# WZ4827R043-V1_0-20230227.net
KiCad netlist of a schematic drawn in EAGLE
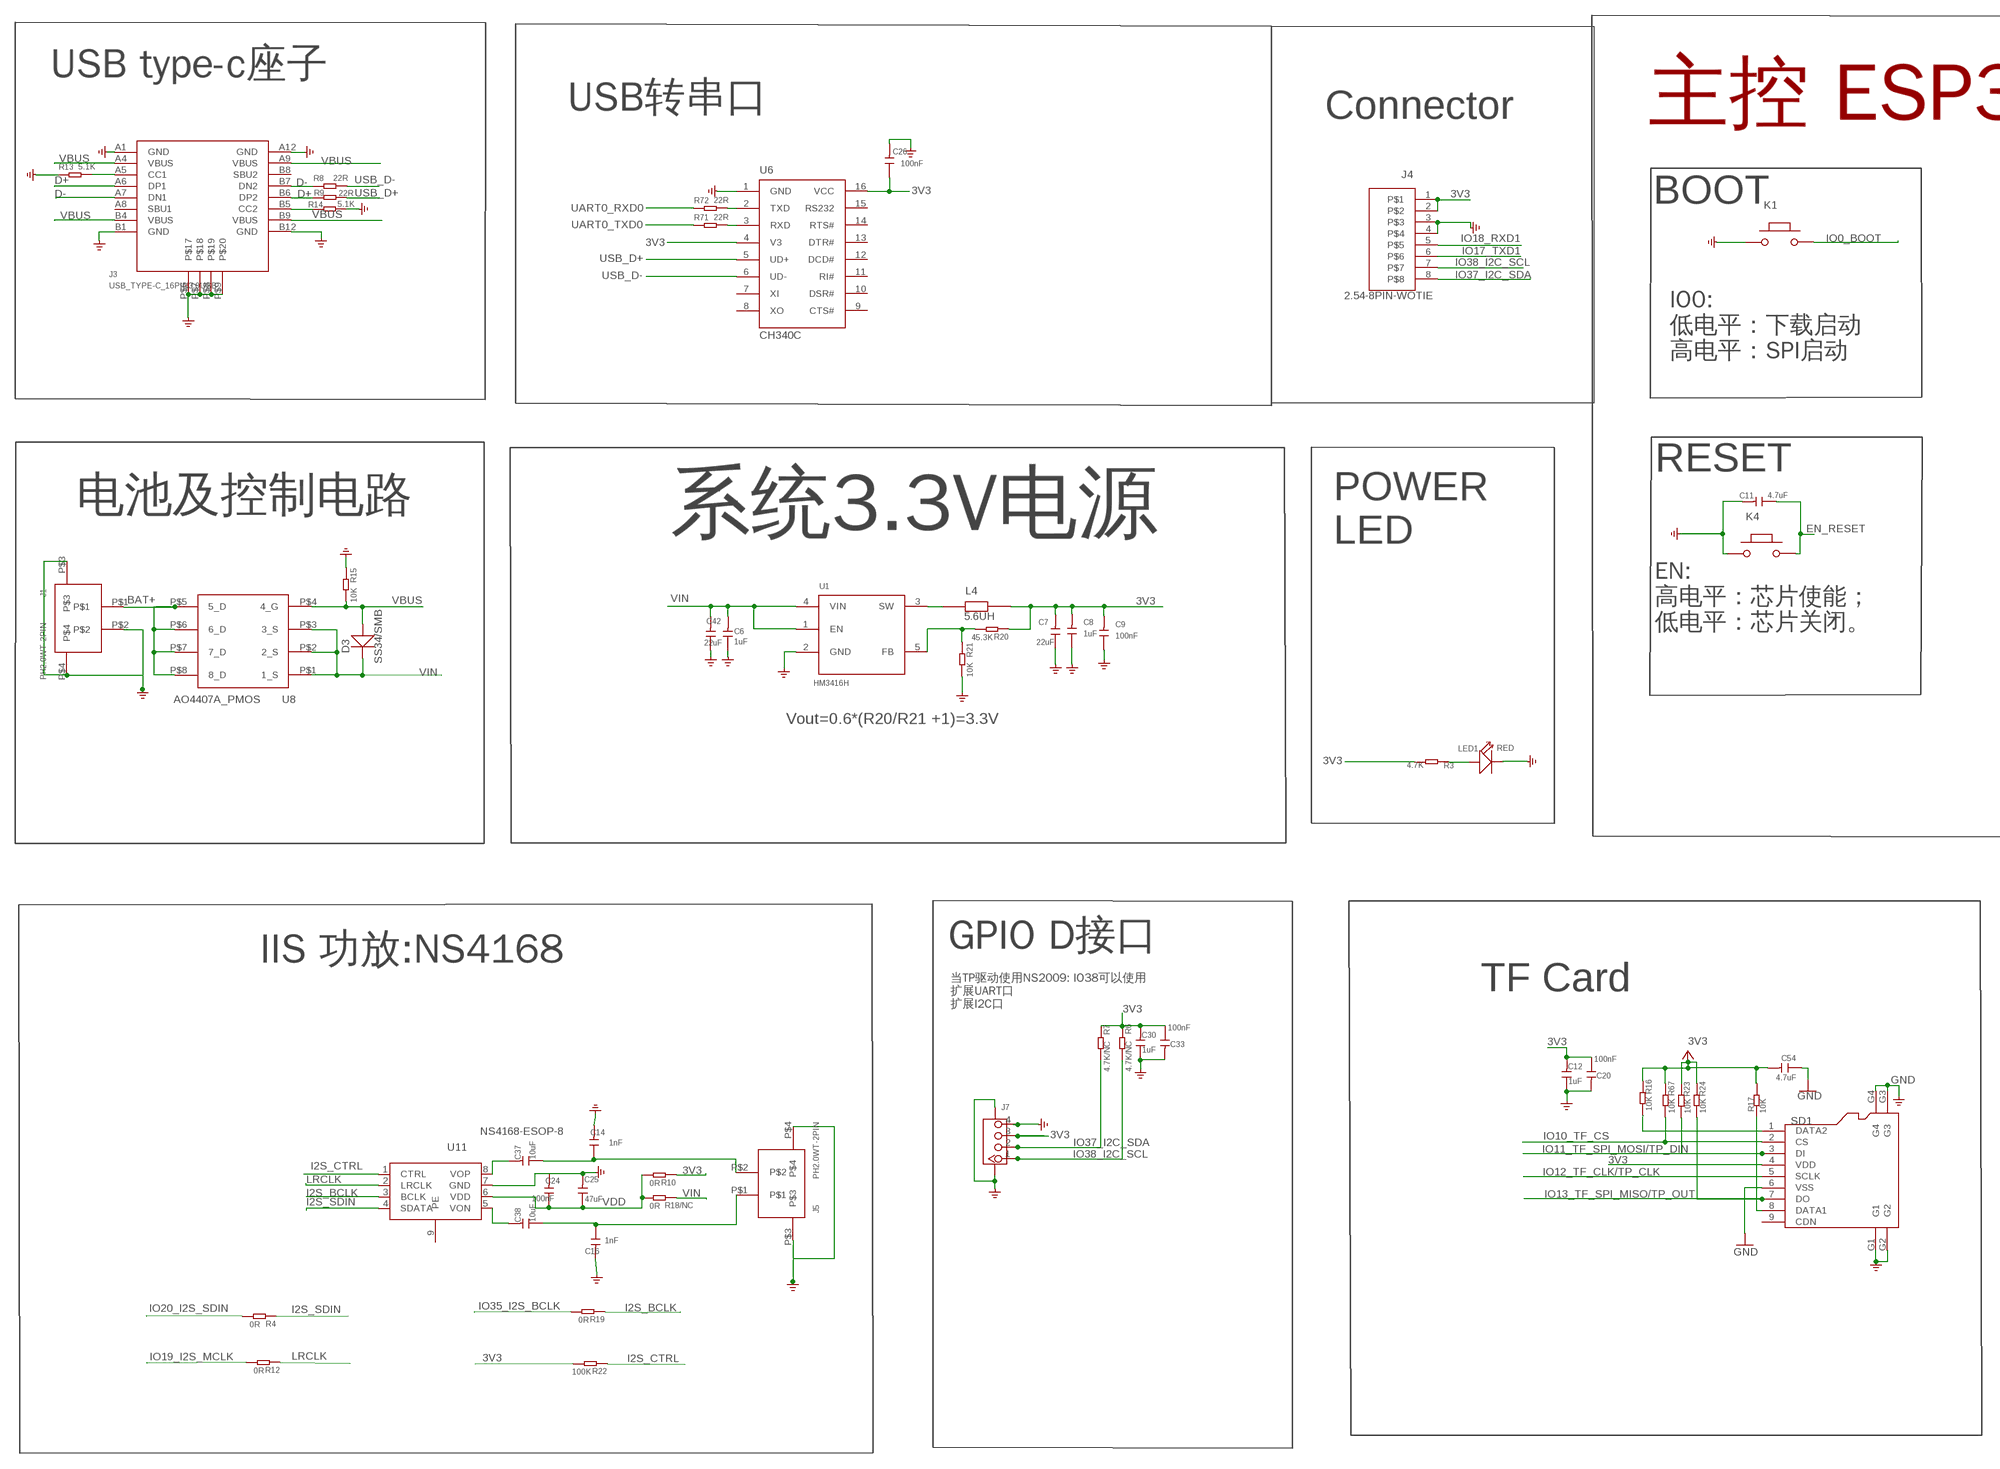
[diagram p0: schematic, sheet 1, part 1 of 2]
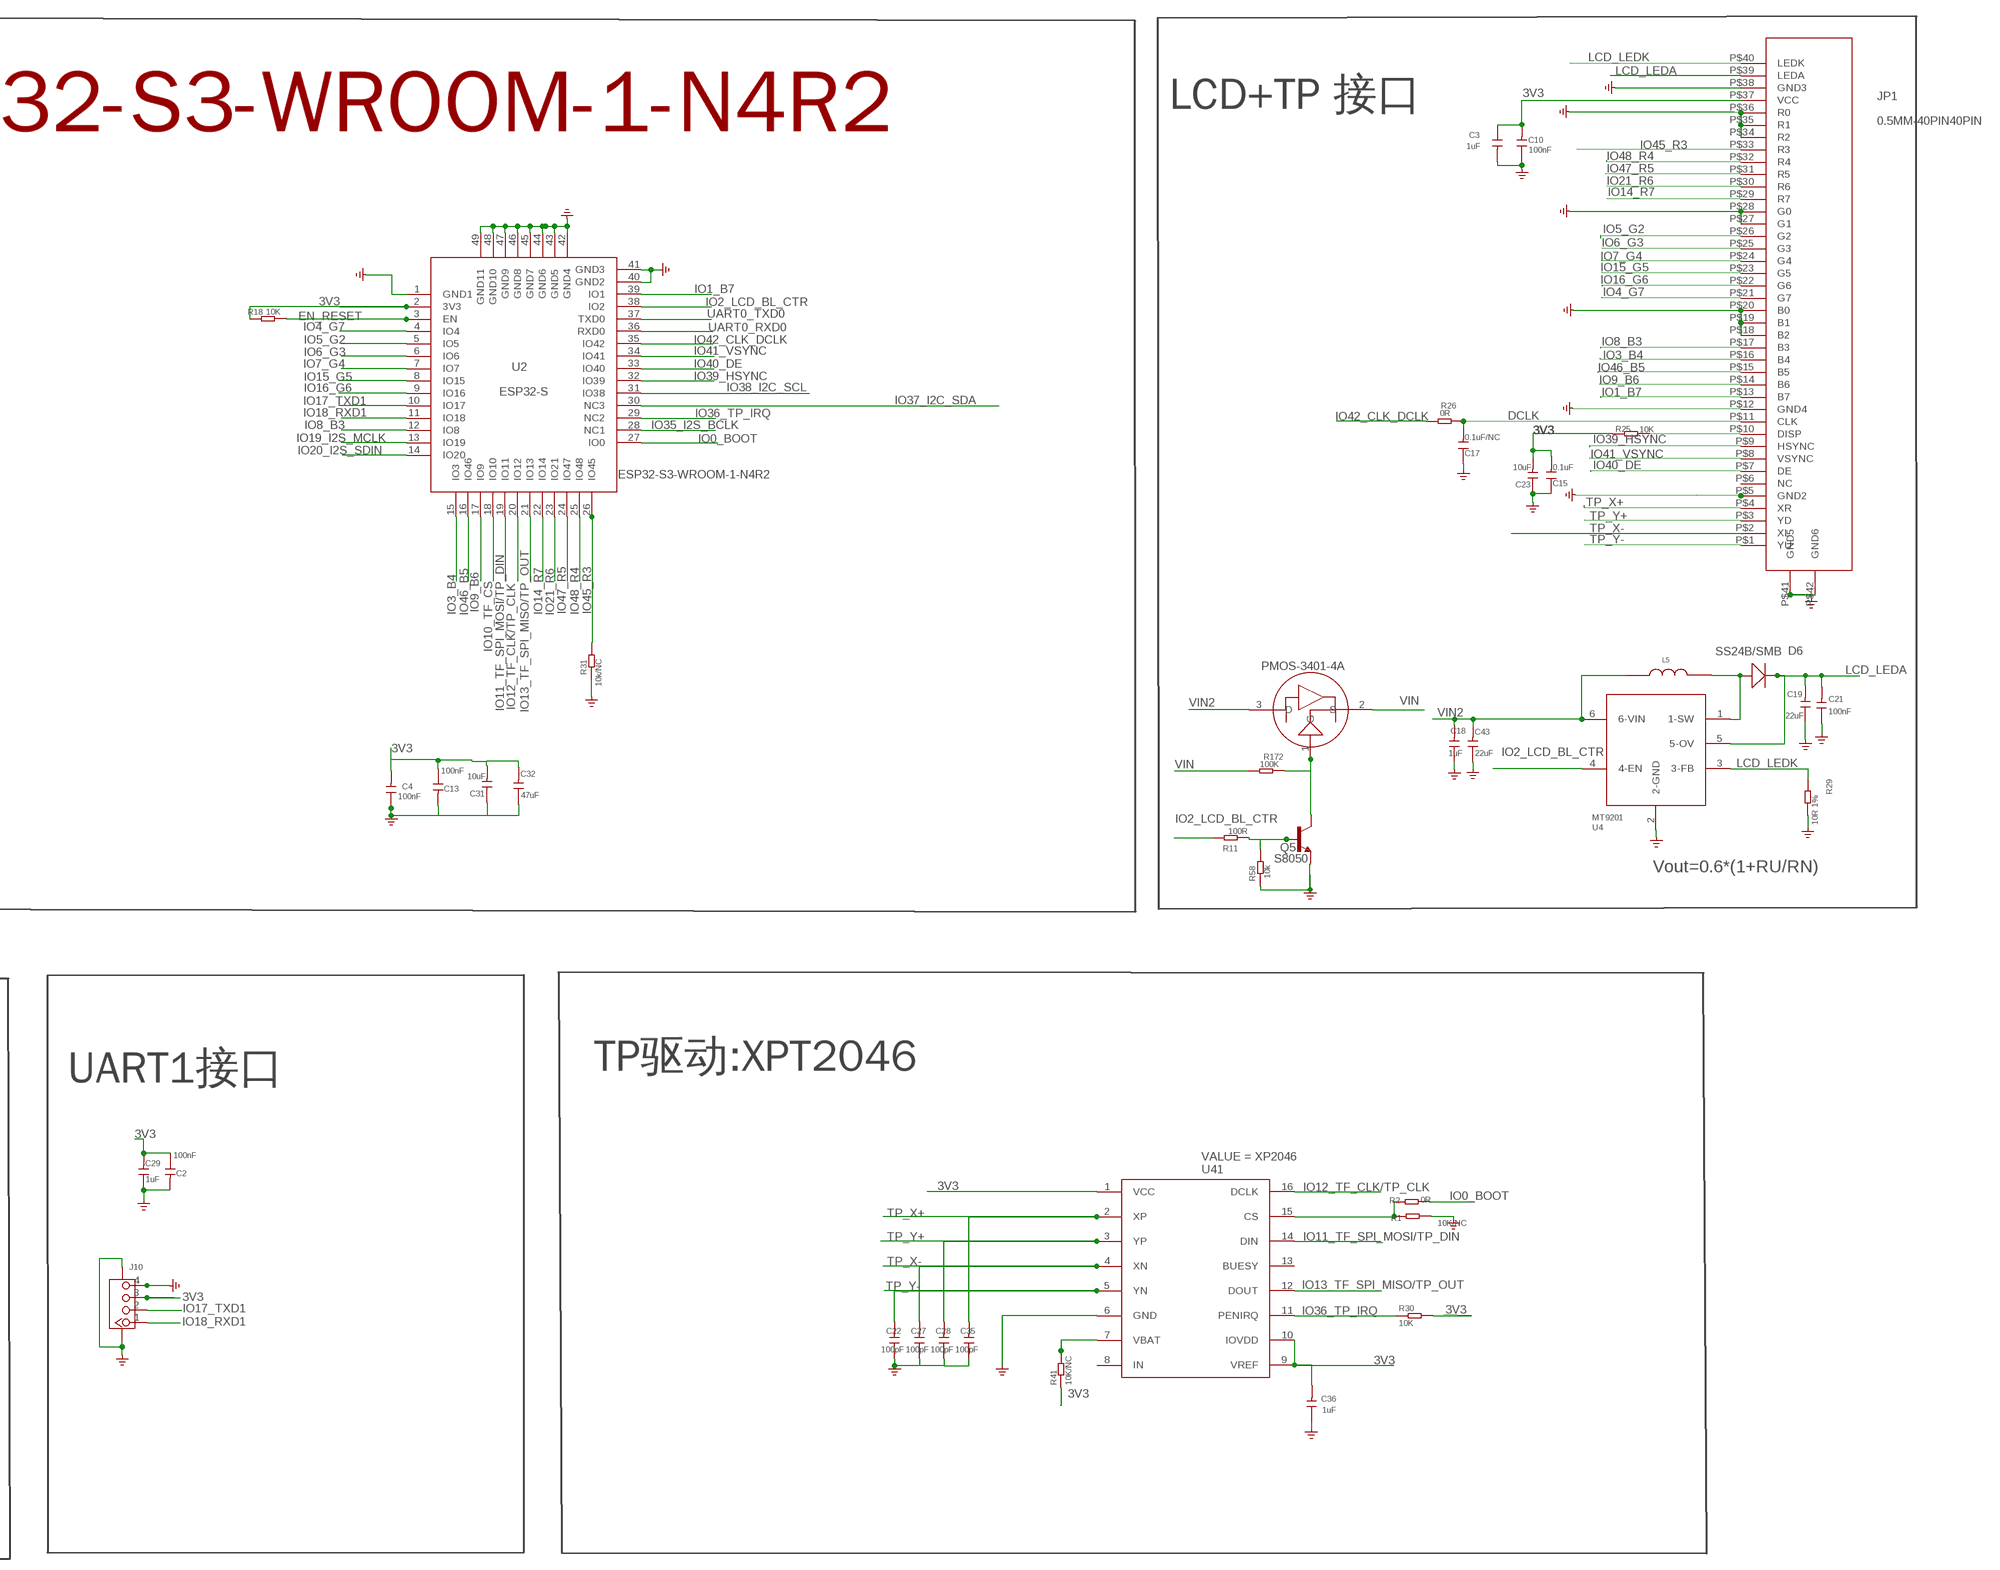
[diagram p1: schematic, sheet 1, part 2 of 2]

(export (version "E")
  (design (tool "Eeschema 10.0.6"))
  (components
    (comp (ref "C2")
      (value "100nF")
      (footprint "eagle-import:C0603")
      (libsource (lib "eagle-import") (part "C-0603"))
    )
    (comp (ref "C3")
      (value "1uF")
      (footprint "eagle-import:C0603")
      (libsource (lib "eagle-import") (part "C-0603"))
    )
    (comp (ref "C4")
      (value "100nF")
      (footprint "eagle-import:C0603")
      (libsource (lib "eagle-import") (part "C-0603"))
    )
    (comp (ref "C6")
      (value "1uF")
      (footprint "eagle-import:0603")
      (libsource (lib "eagle-import") (part "C0603"))
    )
    (comp (ref "C7")
      (value "22uF")
      (footprint "eagle-import:0805")
      (libsource (lib "eagle-import") (part "C0805"))
    )
    (comp (ref "C8")
      (value "1uF")
      (footprint "eagle-import:0603")
      (libsource (lib "eagle-import") (part "C0603"))
    )
    (comp (ref "C9")
      (value "100nF")
      (footprint "eagle-import:0603")
      (libsource (lib "eagle-import") (part "C0603"))
    )
    (comp (ref "C10")
      (value "100nF")
      (footprint "eagle-import:C0603")
      (libsource (lib "eagle-import") (part "C-0603"))
    )
    (comp (ref "C11")
      (value "4.7uF")
      (footprint "eagle-import:0603")
      (libsource (lib "eagle-import") (part "C0603"))
    )
    (comp (ref "C12")
      (value "1uF")
      (footprint "eagle-import:DISCRETE_C0603")
      (libsource (lib "eagle-import") (part "A_xbj_DISCRETE_C-0603"))
    )
    (comp (ref "C13")
      (value "100nF")
      (footprint "eagle-import:C0603")
      (libsource (lib "eagle-import") (part "C-0603"))
    )
    (comp (ref "C14")
      (value "1nF")
      (footprint "eagle-import:C0603")
      (libsource (lib "eagle-import") (part "C-0603"))
    )
    (comp (ref "C15")
      (value "0.1uF")
      (footprint "eagle-import:DISCRETE_C0603")
      (libsource (lib "eagle-import") (part "DISCRETE_C-0603"))
    )
    (comp (ref "C16")
      (value "1nF")
      (footprint "eagle-import:C0603")
      (libsource (lib "eagle-import") (part "C-0603"))
    )
    (comp (ref "C17")
      (value "0.1uF/NC")
      (footprint "eagle-import:DISCRETE_C0603")
      (libsource (lib "eagle-import") (part "DISCRETE_C-0603"))
    )
    (comp (ref "C18")
      (value "1uF")
      (footprint "eagle-import:0603")
      (libsource (lib "eagle-import") (part "C0603"))
    )
    (comp (ref "C19")
      (value "22uF")
      (footprint "eagle-import:0805")
      (libsource (lib "eagle-import") (part "C0805"))
    )
    (comp (ref "C20")
      (value "100nF")
      (footprint "eagle-import:C0603")
      (libsource (lib "eagle-import") (part "C-0603"))
    )
    (comp (ref "C21")
      (value "100nF")
      (footprint "eagle-import:0603")
      (libsource (lib "eagle-import") (part "C0603"))
    )
    (comp (ref "C22")
      (value "100pF")
      (footprint "eagle-import:0603")
      (libsource (lib "eagle-import") (part "C0603"))
    )
    (comp (ref "C23")
      (value "10uF")
      (footprint "eagle-import:DISCRETE_C0603")
      (libsource (lib "eagle-import") (part "DISCRETE_C-0603"))
    )
    (comp (ref "C24")
      (value "100nF")
      (footprint "eagle-import:C0603")
      (libsource (lib "eagle-import") (part "C-0603"))
    )
    (comp (ref "C25")
      (value "47uF")
      (footprint "eagle-import:0805")
      (libsource (lib "eagle-import") (part "C0805"))
    )
    (comp (ref "C26")
      (value "100nF")
      (footprint "eagle-import:0603")
      (libsource (lib "eagle-import") (part "C0603"))
    )
    (comp (ref "C27")
      (value "100pF")
      (footprint "eagle-import:0603")
      (libsource (lib "eagle-import") (part "C0603"))
    )
    (comp (ref "C28")
      (value "100pF")
      (footprint "eagle-import:0603")
      (libsource (lib "eagle-import") (part "C0603"))
    )
    (comp (ref "C29")
      (value "1uF")
      (footprint "eagle-import:DISCRETE_C0603")
      (libsource (lib "eagle-import") (part "A_xbj_DISCRETE_C-0603"))
    )
    (comp (ref "C30")
      (value "1uF")
      (footprint "eagle-import:DISCRETE_C0603")
      (libsource (lib "eagle-import") (part "A_xbj_DISCRETE_C-0603"))
    )
    (comp (ref "C31")
      (value "10uF")
      (footprint "eagle-import:DISCRETE_C0603")
      (libsource (lib "eagle-import") (part "DISCRETE_C-0603"))
    )
    (comp (ref "C32")
      (value "47uF")
      (footprint "eagle-import:0805")
      (libsource (lib "eagle-import") (part "C0805"))
    )
    (comp (ref "C33")
      (value "100nF")
      (footprint "eagle-import:C0603")
      (libsource (lib "eagle-import") (part "C-0603"))
    )
    (comp (ref "C35")
      (value "100pF")
      (footprint "eagle-import:0603")
      (libsource (lib "eagle-import") (part "C0603"))
    )
    (comp (ref "C36")
      (value "1uF")
      (footprint "eagle-import:DISCRETE_C0603")
      (libsource (lib "eagle-import") (part "A_xbj_DISCRETE_C-0603"))
    )
    (comp (ref "C37")
      (value "10uF")
      (footprint "eagle-import:DISCRETE_C0603")
      (libsource (lib "eagle-import") (part "A_xbj_DISCRETE_C-0603"))
    )
    (comp (ref "C38")
      (value "10uF")
      (footprint "eagle-import:DISCRETE_C0603")
      (libsource (lib "eagle-import") (part "A_xbj_DISCRETE_C-0603"))
    )
    (comp (ref "C42")
      (value "22uF")
      (footprint "eagle-import:0805")
      (libsource (lib "eagle-import") (part "C0805"))
    )
    (comp (ref "C43")
      (value "22uF")
      (footprint "eagle-import:0805")
      (libsource (lib "eagle-import") (part "C0805"))
    )
    (comp (ref "C54")
      (value "4.7uF")
      (footprint "eagle-import:DISCRETE_C0603")
      (libsource (lib "eagle-import") (part "DISCRETE_C-0603"))
    )
    (comp (ref "D3")
      (value "SS34/SMB")
      (footprint "eagle-import:214AB")
      (libsource (lib "eagle-import") (part "214ABDO-214AB"))
    )
    (comp (ref "D6")
      (value "SS24B/SMB")
      (footprint "eagle-import:214AB")
      (libsource (lib "eagle-import") (part "214ABDO-214AB"))
    )
    (comp (ref "J1")
      (value "PH2.0WT-2PIN")
      (footprint "eagle-import:PH2.0WT-2PIN")
      (libsource (lib "eagle-import") (part "PH2.0WT-2PIN"))
    )
    (comp (ref "J3")
      (value "USB_TYPE-C_16PIN3.0USB")
      (footprint "eagle-import:KEVIN_3.0TYPEC-SMD")
      (libsource (lib "eagle-import") (part "USB_TYPE-C_16PIN3.0USB"))
    )
    (comp (ref "J4")
      (value "2.54-8PIN-WOTIE")
      (footprint "eagle-import:2.54-8P-WOTIE")
      (libsource (lib "eagle-import") (part "2.54-8PIN-WOTIE"))
    )
    (comp (ref "J5")
      (value "PH2.0WT-2PIN")
      (footprint "eagle-import:PH2.0WT-2PIN")
      (libsource (lib "eagle-import") (part "PH2.0WT-2PIN"))
    )
    (comp (ref "J7")
      (value "CONNECTOR_TWIG-4P-2.0-SMD-FEMALE-REINFORCE90D")
      (footprint "eagle-import:CONNECTOR_4P-SMD-2.0-90D")
      (libsource (lib "eagle-import") (part "CONNECTOR_TWIG-4P-2.0-SMD-FEMALE-REINFORCE90D"))
    )
    (comp (ref "J10")
      (value "CONNECTOR_TWIG-4P-2.0-SMD-FEMALE-REINFORCE90D")
      (footprint "eagle-import:CONNECTOR_4P-SMD-2.0-90D")
      (libsource (lib "eagle-import") (part "CONNECTOR_TWIG-4P-2.0-SMD-FEMALE-REINFORCE90D"))
    )
    (comp (ref "JP1")
      (value "0.5MM-40PIN40PIN")
      (footprint "eagle-import:0.5MM_40P")
      (libsource (lib "eagle-import") (part "0.5MM-40PIN40PIN"))
    )
    (comp (ref "K1")
      (value "BUTTON")
      (footprint "eagle-import:157SW")
      (libsource (lib "eagle-import") (part "PB157"))
    )
    (comp (ref "K4")
      (value "BUTTON")
      (footprint "eagle-import:157SW")
      (libsource (lib "eagle-import") (part "PB157"))
    )
    (comp (ref "L4")
      (value "5.6UH")
      (footprint "eagle-import:CD54")
      (libsource (lib "eagle-import") (part "CROWPI2-MB-V1.4-20211012_CMP201209UD1R0MT"))
    )
    (comp (ref "L5")
      (value "CD32_6.8uH")
      (footprint "eagle-import:CD32")
      (libsource (lib "eagle-import") (part "CD32_950MA"))
    )
    (comp (ref "LED1")
      (value "RED")
      (footprint "eagle-import:DISCRETE_LED-0603")
      (libsource (lib "eagle-import") (part "DISCRETE_LED0603"))
    )
    (comp (ref "Q5")
      (value "S8050")
      (footprint "eagle-import:SPARKFUN_SOT23")
      (libsource (lib "eagle-import") (part "SPARKFUN_TRANSISTOR_NPNSOT23"))
    )
    (comp (ref "Q30")
      (value "PMOS-3401-4A")
      (footprint "eagle-import:SOT-23")
      (libsource (lib "eagle-import") (part "P-MOS-SOT23"))
    )
    (comp (ref "R1")
      (value "10K/NC")
      (footprint "eagle-import:R0603")
      (libsource (lib "eagle-import") (part "R0603"))
    )
    (comp (ref "R2")
      (value "0R")
      (footprint "eagle-import:DISCRETE_R0603")
      (libsource (lib "eagle-import") (part "Crowtail-_LED-V2.0-20190615-01_DISCRETE_R-0603"))
    )
    (comp (ref "R3")
      (value "4.7K")
      (footprint "eagle-import:DISCRETE_R0603")
      (libsource (lib "eagle-import") (part "Crowtail-_LED-V2.0-20190615-01_DISCRETE_R-0603"))
    )
    (comp (ref "R4")
      (value "0R")
      (footprint "eagle-import:DISCRETE_R0603")
      (libsource (lib "eagle-import") (part "Crowtail-_LED-V2.0-20190615-01_DISCRETE_R-0603"))
    )
    (comp (ref "R6")
      (value "4.7K/NC")
      (footprint "eagle-import:DISCRETE_R0603")
      (libsource (lib "eagle-import") (part "Crowtail-_LED-V2.0-20190615-01_DISCRETE_R-0603"))
    )
    (comp (ref "R7")
      (value "4.7K/NC")
      (footprint "eagle-import:DISCRETE_R0603")
      (libsource (lib "eagle-import") (part "Crowtail-_LED-V2.0-20190615-01_DISCRETE_R-0603"))
    )
    (comp (ref "R8")
      (value "22R")
      (footprint "eagle-import:DISCRETE_R0603")
      (libsource (lib "eagle-import") (part "Crowtail-_LED-V2.0-20190615-01_DISCRETE_R-0603"))
    )
    (comp (ref "R9")
      (value "22R")
      (footprint "eagle-import:DISCRETE_R0603")
      (libsource (lib "eagle-import") (part "Crowtail-_LED-V2.0-20190615-01_DISCRETE_R-0603"))
    )
    (comp (ref "R10")
      (value "0R")
      (footprint "eagle-import:DISCRETE_R0603")
      (libsource (lib "eagle-import") (part "Crowtail-_LED-V2.0-20190615-01_DISCRETE_R-0603"))
    )
    (comp (ref "R11")
      (value "100R")
      (footprint "eagle-import:R0603")
      (libsource (lib "eagle-import") (part "R0603"))
    )
    (comp (ref "R12")
      (value "0R")
      (footprint "eagle-import:DISCRETE_R0603")
      (libsource (lib "eagle-import") (part "Crowtail-_LED-V2.0-20190615-01_DISCRETE_R-0603"))
    )
    (comp (ref "R13")
      (value "5.1K")
      (footprint "eagle-import:DISCRETE_R0603")
      (libsource (lib "eagle-import") (part "Crowtail-_LED-V2.0-20190615-01_DISCRETE_R-0603"))
    )
    (comp (ref "R14")
      (value "5.1K")
      (footprint "eagle-import:DISCRETE_R0603")
      (libsource (lib "eagle-import") (part "Crowtail-_LED-V2.0-20190615-01_DISCRETE_R-0603"))
    )
    (comp (ref "R15")
      (value "10K")
      (footprint "eagle-import:DISCRETE_R0603")
      (libsource (lib "eagle-import") (part "Crowtail-_LED-V2.0-20190615-01_DISCRETE_R-0603"))
    )
    (comp (ref "R16")
      (value "10K")
      (footprint "eagle-import:DISCRETE_R0603")
      (libsource (lib "eagle-import") (part "Crowtail-_LED-V2.0-20190615-01_DISCRETE_R-0603"))
    )
    (comp (ref "R17")
      (value "10K")
      (footprint "eagle-import:DISCRETE_R0603")
      (libsource (lib "eagle-import") (part "Crowtail-_LED-V2.0-20190615-01_DISCRETE_R-0603"))
    )
    (comp (ref "R18")
      (value "10K")
      (footprint "eagle-import:DISCRETE_R0603")
      (libsource (lib "eagle-import") (part "Crowtail-_LED-V2.0-20190615-01_DISCRETE_R-0603"))
    )
    (comp (ref "R18/NC")
      (value "0R")
      (footprint "eagle-import:DISCRETE_R0603")
      (libsource (lib "eagle-import") (part "Crowtail-_LED-V2.0-20190615-01_DISCRETE_R-0603"))
    )
    (comp (ref "R19")
      (value "0R")
      (footprint "eagle-import:DISCRETE_R0603")
      (libsource (lib "eagle-import") (part "Crowtail-_LED-V2.0-20190615-01_DISCRETE_R-0603"))
    )
    (comp (ref "R20")
      (value "45.3K")
      (footprint "eagle-import:DISCRETE_R0603")
      (libsource (lib "eagle-import") (part "Crowtail-_LED-V2.0-20190615-01_DISCRETE_R-0603"))
    )
    (comp (ref "R21")
      (value "10K")
      (footprint "eagle-import:DISCRETE_R0603")
      (libsource (lib "eagle-import") (part "Crowtail-_LED-V2.0-20190615-01_DISCRETE_R-0603"))
    )
    (comp (ref "R22")
      (value "100K")
      (footprint "eagle-import:DISCRETE_R0603")
      (libsource (lib "eagle-import") (part "Crowtail-_LED-V2.0-20190615-01_DISCRETE_R-0603"))
    )
    (comp (ref "R23")
      (value "10K")
      (footprint "eagle-import:DISCRETE_R0603")
      (libsource (lib "eagle-import") (part "Crowtail-_LED-V2.0-20190615-01_DISCRETE_R-0603"))
    )
    (comp (ref "R24")
      (value "10K")
      (footprint "eagle-import:DISCRETE_R0603")
      (libsource (lib "eagle-import") (part "Crowtail-_LED-V2.0-20190615-01_DISCRETE_R-0603"))
    )
    (comp (ref "R25")
      (value "10K")
      (footprint "eagle-import:DISCRETE_R0603")
      (libsource (lib "eagle-import") (part "Crowtail-_LED-V2.0-20190615-01_DISCRETE_R-0603"))
    )
    (comp (ref "R26")
      (value "0R")
      (footprint "eagle-import:R0603")
      (libsource (lib "eagle-import") (part "R-0603"))
    )
    (comp (ref "R29")
      (value "10R 1%")
      (footprint "eagle-import:DISCRETE_R0603")
      (libsource (lib "eagle-import") (part "Crowtail-_LED-V2.0-20190615-01_DISCRETE_R-0603"))
    )
    (comp (ref "R30")
      (value "10K")
      (footprint "eagle-import:DISCRETE_R0603")
      (libsource (lib "eagle-import") (part "DISCRETE_R-0603"))
    )
    (comp (ref "R31")
      (value "10k/NC")
      (footprint "eagle-import:R0603")
      (libsource (lib "eagle-import") (part "R0603"))
    )
    (comp (ref "R41")
      (value "10K/NC")
      (footprint "eagle-import:DISCRETE_R0603")
      (libsource (lib "eagle-import") (part "DISCRETE_R-0603"))
    )
    (comp (ref "R58")
      (value "10k")
      (footprint "eagle-import:R0603")
      (libsource (lib "eagle-import") (part "R0603"))
    )
    (comp (ref "R67")
      (value "10K")
      (footprint "eagle-import:DISCRETE_R0603")
      (libsource (lib "eagle-import") (part "Crowtail-_LED-V2.0-20190615-01_DISCRETE_R-0603"))
    )
    (comp (ref "R71")
      (value "22R")
      (footprint "eagle-import:DISCRETE_R0603")
      (libsource (lib "eagle-import") (part "Crowtail-_LED-V2.0-20190615-01_DISCRETE_R-0603"))
    )
    (comp (ref "R72")
      (value "22R")
      (footprint "eagle-import:DISCRETE_R0603")
      (libsource (lib "eagle-import") (part "Crowtail-_LED-V2.0-20190615-01_DISCRETE_R-0603"))
    )
    (comp (ref "R172")
      (value "100K")
      (footprint "eagle-import:R0603")
      (libsource (lib "eagle-import") (part "R-0603"))
    )
    (comp (ref "SD1")
      (value "HOLDER-MICROSD-9P")
      (footprint "eagle-import:9P-SMD-W_-RING")
      (libsource (lib "eagle-import") (part "HOLDER-MICROSD-9P"))
    )
    (comp (ref "U1")
      (value "HM3416H")
      (footprint "eagle-import:A_XBJ_SOT23-5")
      (libsource (lib "eagle-import") (part "A_XBJ_HM3420B"))
    )
    (comp (ref "U2")
      (value "ESP32-S")
      (footprint "eagle-import:ESP32-S3")
      (fields (field (name "U2") "ESP32-S3-WROOM-1-N4R2"))
      (libsource (lib "eagle-import") (part "ESP32-S"))
    )
    (comp (ref "U4")
      (value "MT9201")
      (footprint "eagle-import:SOT23-6")
      (libsource (lib "eagle-import") (part "MT9201"))
    )
    (comp (ref "U6")
      (value "CH340C")
      (footprint "eagle-import:SOP-16")
      (libsource (lib "eagle-import") (part "CH340G"))
    )
    (comp (ref "U8")
      (value "AO4407A_PMOS")
      (footprint "eagle-import:SOP8")
      (libsource (lib "eagle-import") (part "T_PMOS_AO4407A_SOP8"))
    )
    (comp (ref "U11")
      (value "NS4168-ESOP-8")
      (footprint "eagle-import:NS4168-ESOP-8")
      (libsource (lib "eagle-import") (part "NS4168-ESOP-8"))
    )
    (comp (ref "U41")
      (value "XP2046")
      (footprint "eagle-import:XP2046-SSOP16")
      (libsource (lib "eagle-import") (part "XP2046"))
    )
  )
  (nets
    (net (code "1") (name "+3V3") (class "Default")
      (node (ref "C10") (pin "2") (pinfunction "2_2") (pintype "passive"))
      (node (ref "C12") (pin "2") (pinfunction "2_2") (pintype "passive"))
      (node (ref "C13") (pin "1") (pinfunction "1_1") (pintype "passive"))
      (node (ref "C15") (pin "2") (pinfunction "2_2") (pintype "passive"))
      (node (ref "C2") (pin "1") (pinfunction "1_1") (pintype "passive"))
      (node (ref "C20") (pin "1") (pinfunction "1_1") (pintype "passive"))
      (node (ref "C23") (pin "2") (pinfunction "2_2") (pintype "passive"))
      (node (ref "C26") (pin "1") (pinfunction "1_1") (pintype "passive"))
      (node (ref "C29") (pin "2") (pinfunction "2_2") (pintype "passive"))
      (node (ref "C3") (pin "1") (pinfunction "1_1") (pintype "passive"))
      (node (ref "C30") (pin "2") (pinfunction "2_2") (pintype "passive"))
      (node (ref "C31") (pin "2") (pinfunction "2_2") (pintype "passive"))
      (node (ref "C32") (pin "2") (pinfunction "2_2") (pintype "passive"))
      (node (ref "C33") (pin "1") (pinfunction "1_1") (pintype "passive"))
      (node (ref "C36") (pin "2") (pinfunction "2_2") (pintype "passive"))
      (node (ref "C4") (pin "2") (pinfunction "2_2") (pintype "passive"))
      (node (ref "C54") (pin "2") (pinfunction "2_2") (pintype "passive"))
      (node (ref "C7") (pin "2") (pinfunction "2_2") (pintype "passive"))
      (node (ref "C8") (pin "2") (pinfunction "2_2") (pintype "passive"))
      (node (ref "C9") (pin "2") (pinfunction "2_2") (pintype "passive"))
      (node (ref "J10") (pin "3") (pinfunction "3_3") (pintype "bidirectional"))
      (node (ref "J4") (pin "1") (pinfunction "P$1_1") (pintype "bidirectional"))
      (node (ref "J4") (pin "2") (pinfunction "P$2_2") (pintype "bidirectional"))
      (node (ref "J7") (pin "3") (pinfunction "3_3") (pintype "bidirectional"))
      (node (ref "JP1") (pin "P$37") (pinfunction "VCC_P$37") (pintype "bidirectional"))
      (node (ref "L4") (pin "2") (pinfunction "2_2") (pintype "bidirectional"))
      (node (ref "R10") (pin "1") (pinfunction "1_1") (pintype "passive"))
      (node (ref "R16") (pin "1") (pinfunction "1_1") (pintype "passive"))
      (node (ref "R17") (pin "1") (pinfunction "1_1") (pintype "passive"))
      (node (ref "R18") (pin "1") (pinfunction "1_1") (pintype "passive"))
      (node (ref "R20") (pin "1") (pinfunction "1_1") (pintype "passive"))
      (node (ref "R22") (pin "2") (pinfunction "2_2") (pintype "passive"))
      (node (ref "R23") (pin "1") (pinfunction "1_1") (pintype "passive"))
      (node (ref "R24") (pin "1") (pinfunction "1_1") (pintype "passive"))
      (node (ref "R25") (pin "1") (pinfunction "1_1") (pintype "passive"))
      (node (ref "R3") (pin "2") (pinfunction "2_2") (pintype "passive"))
      (node (ref "R30") (pin "2") (pinfunction "2_2") (pintype "passive"))
      (node (ref "R41") (pin "1") (pinfunction "1_1") (pintype "passive"))
      (node (ref "R6") (pin "1") (pinfunction "1_1") (pintype "passive"))
      (node (ref "R67") (pin "1") (pinfunction "1_1") (pintype "passive"))
      (node (ref "R7") (pin "1") (pinfunction "1_1") (pintype "passive"))
      (node (ref "SD1") (pin "4") (pinfunction "VDD_4") (pintype "bidirectional"))
      (node (ref "U2") (pin "2") (pinfunction "3V3_2") (pintype "bidirectional"))
      (node (ref "U41") (pin "1") (pinfunction "VCC_1") (pintype "bidirectional"))
      (node (ref "U41") (pin "10") (pinfunction "IOVDD_10") (pintype "bidirectional"))
      (node (ref "U41") (pin "9") (pinfunction "VREF_9") (pintype "bidirectional"))
      (node (ref "U6") (pin "16") (pinfunction "VCC_16") (pintype "bidirectional"))
      (node (ref "U6") (pin "4") (pinfunction "V3_4") (pintype "bidirectional"))
    )
    (net (code "2") (name "/BAT+") (class "Default")
      (node (ref "J1") (pin "P$1") (pinfunction "P$1_P$1") (pintype "bidirectional"))
      (node (ref "U8") (pin "P$5") (pinfunction "5_D_P$5") (pintype "bidirectional"))
      (node (ref "U8") (pin "P$6") (pinfunction "6_D_P$6") (pintype "bidirectional"))
      (node (ref "U8") (pin "P$7") (pinfunction "7_D_P$7") (pintype "bidirectional"))
      (node (ref "U8") (pin "P$8") (pinfunction "8_D_P$8") (pintype "bidirectional"))
    )
    (net (code "3") (name "/D+") (class "Default")
      (node (ref "J3") (pin "A6") (pinfunction "DP1_A6") (pintype "bidirectional"))
      (node (ref "J3") (pin "B6") (pinfunction "DP2_B6") (pintype "bidirectional"))
      (node (ref "R9") (pin "1") (pinfunction "1_1") (pintype "passive"))
    )
    (net (code "4") (name "/D-") (class "Default")
      (node (ref "J3") (pin "A7") (pinfunction "DN1_A7") (pintype "bidirectional"))
      (node (ref "J3") (pin "B7") (pinfunction "DN2_B7") (pintype "bidirectional"))
      (node (ref "R8") (pin "1") (pinfunction "1_1") (pintype "passive"))
    )
    (net (code "5") (name "/DCLK") (class "Default")
      (node (ref "C17") (pin "2") (pinfunction "2_2") (pintype "passive"))
      (node (ref "JP1") (pin "P$11") (pinfunction "CLK_P$11") (pintype "bidirectional"))
      (node (ref "R26") (pin "2") (pinfunction "2_2") (pintype "passive"))
    )
    (net (code "6") (name "/EN_RESET") (class "Default")
      (node (ref "C11") (pin "1") (pinfunction "1_1") (pintype "passive"))
      (node (ref "K4") (pin "2") (pinfunction "2_2") (pintype "passive"))
      (node (ref "R18") (pin "2") (pinfunction "2_2") (pintype "passive"))
      (node (ref "U2") (pin "3") (pinfunction "EN_3") (pintype "bidirectional"))
    )
    (net (code "7") (name "/I2S_BCLK") (class "Default")
      (node (ref "R19") (pin "1") (pinfunction "1_1") (pintype "passive"))
      (node (ref "U11") (pin "3") (pinfunction "BCLK_3") (pintype "bidirectional"))
    )
    (net (code "8") (name "/I2S_CTRL") (class "Default")
      (node (ref "R22") (pin "1") (pinfunction "1_1") (pintype "passive"))
      (node (ref "U11") (pin "1") (pinfunction "CTRL_1") (pintype "bidirectional"))
    )
    (net (code "9") (name "/I2S_SDIN") (class "Default")
      (node (ref "R4") (pin "1") (pinfunction "1_1") (pintype "passive"))
      (node (ref "U11") (pin "4") (pinfunction "SDATA_4") (pintype "bidirectional"))
    )
    (net (code "10") (name "/IO0_BOOT") (class "Default")
      (node (ref "K1") (pin "2") (pinfunction "2_2") (pintype "passive"))
      (node (ref "R2") (pin "1") (pinfunction "1_1") (pintype "passive"))
      (node (ref "U2") (pin "27") (pinfunction "IO0_27") (pintype "bidirectional"))
    )
    (net (code "11") (name "/IO1_B7") (class "Default")
      (node (ref "JP1") (pin "P$13") (pinfunction "B7_P$13") (pintype "bidirectional"))
      (node (ref "U2") (pin "39") (pinfunction "IO1_39") (pintype "bidirectional"))
    )
    (net (code "12") (name "/IO2_LCD_BL_CTR") (class "Default")
      (node (ref "R11") (pin "2") (pinfunction "2_2") (pintype "passive"))
      (node (ref "U2") (pin "38") (pinfunction "IO2_38") (pintype "bidirectional"))
      (node (ref "U4") (pin "4") (pinfunction "4-EN_4") (pintype "bidirectional"))
    )
    (net (code "13") (name "/IO3_B4") (class "Default")
      (node (ref "JP1") (pin "P$16") (pinfunction "B4_P$16") (pintype "bidirectional"))
      (node (ref "U2") (pin "15") (pinfunction "IO3_15") (pintype "bidirectional"))
    )
    (net (code "14") (name "/IO4_G7") (class "Default")
      (node (ref "JP1") (pin "P$21") (pinfunction "G7_P$21") (pintype "bidirectional"))
      (node (ref "U2") (pin "4") (pinfunction "IO4_4") (pintype "bidirectional"))
    )
    (net (code "15") (name "/IO5_G2") (class "Default")
      (node (ref "JP1") (pin "P$26") (pinfunction "G2_P$26") (pintype "bidirectional"))
      (node (ref "U2") (pin "5") (pinfunction "IO5_5") (pintype "bidirectional"))
    )
    (net (code "16") (name "/IO6_G3") (class "Default")
      (node (ref "JP1") (pin "P$25") (pinfunction "G3_P$25") (pintype "bidirectional"))
      (node (ref "U2") (pin "6") (pinfunction "IO6_6") (pintype "bidirectional"))
    )
    (net (code "17") (name "/IO7_G4") (class "Default")
      (node (ref "JP1") (pin "P$24") (pinfunction "G4_P$24") (pintype "bidirectional"))
      (node (ref "U2") (pin "7") (pinfunction "IO7_7") (pintype "bidirectional"))
    )
    (net (code "18") (name "/IO8_B3") (class "Default")
      (node (ref "JP1") (pin "P$17") (pinfunction "B3_P$17") (pintype "bidirectional"))
      (node (ref "U2") (pin "12") (pinfunction "IO8_12") (pintype "bidirectional"))
    )
    (net (code "19") (name "/IO9_B6") (class "Default")
      (node (ref "JP1") (pin "P$14") (pinfunction "B6_P$14") (pintype "bidirectional"))
      (node (ref "U2") (pin "17") (pinfunction "IO9_17") (pintype "bidirectional"))
    )
    (net (code "20") (name "/IO10_TF_CS") (class "Default")
      (node (ref "R67") (pin "2") (pinfunction "2_2") (pintype "passive"))
      (node (ref "SD1") (pin "2") (pinfunction "CS_2") (pintype "bidirectional"))
      (node (ref "U2") (pin "18") (pinfunction "IO10_18") (pintype "bidirectional"))
    )
    (net (code "21") (name "/IO11_TF_SPI_MOSI{slash}TP_DIN") (class "Default")
      (node (ref "R23") (pin "2") (pinfunction "2_2") (pintype "passive"))
      (node (ref "SD1") (pin "3") (pinfunction "DI_3") (pintype "bidirectional"))
      (node (ref "U2") (pin "19") (pinfunction "IO11_19") (pintype "bidirectional"))
      (node (ref "U41") (pin "14") (pinfunction "DIN_14") (pintype "bidirectional"))
    )
    (net (code "22") (name "/IO12_TF_CLK{slash}TP_CLK") (class "Default")
      (node (ref "SD1") (pin "5") (pinfunction "SCLK_5") (pintype "bidirectional"))
      (node (ref "U2") (pin "20") (pinfunction "IO12_20") (pintype "bidirectional"))
      (node (ref "U41") (pin "16") (pinfunction "DCLK_16") (pintype "bidirectional"))
    )
    (net (code "23") (name "/IO13_TF_SPI_MISO{slash}TP_OUT") (class "Default")
      (node (ref "R24") (pin "2") (pinfunction "2_2") (pintype "passive"))
      (node (ref "SD1") (pin "7") (pinfunction "DO_7") (pintype "bidirectional"))
      (node (ref "U2") (pin "21") (pinfunction "IO13_21") (pintype "bidirectional"))
      (node (ref "U41") (pin "12") (pinfunction "DOUT_12") (pintype "bidirectional"))
    )
    (net (code "24") (name "/IO14_R7") (class "Default")
      (node (ref "JP1") (pin "P$29") (pinfunction "R7_P$29") (pintype "bidirectional"))
      (node (ref "U2") (pin "22") (pinfunction "IO14_22") (pintype "bidirectional"))
    )
    (net (code "25") (name "/IO15_G5") (class "Default")
      (node (ref "JP1") (pin "P$23") (pinfunction "G5_P$23") (pintype "bidirectional"))
      (node (ref "U2") (pin "8") (pinfunction "IO15_8") (pintype "bidirectional"))
    )
    (net (code "26") (name "/IO16_G6") (class "Default")
      (node (ref "JP1") (pin "P$22") (pinfunction "G6_P$22") (pintype "bidirectional"))
      (node (ref "U2") (pin "9") (pinfunction "IO16_9") (pintype "bidirectional"))
    )
    (net (code "27") (name "/IO17_TXD1") (class "Default")
      (node (ref "J10") (pin "2") (pinfunction "2_2") (pintype "bidirectional"))
      (node (ref "J4") (pin "6") (pinfunction "P$6_6") (pintype "bidirectional"))
      (node (ref "U2") (pin "10") (pinfunction "IO17_10") (pintype "bidirectional"))
    )
    (net (code "28") (name "/IO18_RXD1") (class "Default")
      (node (ref "J10") (pin "1") (pinfunction "1_1") (pintype "bidirectional"))
      (node (ref "J4") (pin "5") (pinfunction "P$5_5") (pintype "bidirectional"))
      (node (ref "U2") (pin "11") (pinfunction "IO18_11") (pintype "bidirectional"))
    )
    (net (code "29") (name "/IO19_I2S_MCLK") (class "Default")
      (node (ref "R12") (pin "2") (pinfunction "2_2") (pintype "passive"))
      (node (ref "U2") (pin "13") (pinfunction "IO19_13") (pintype "bidirectional"))
    )
    (net (code "30") (name "/IO20_I2S_SDIN") (class "Default")
      (node (ref "R4") (pin "2") (pinfunction "2_2") (pintype "passive"))
      (node (ref "U2") (pin "14") (pinfunction "IO20_14") (pintype "bidirectional"))
    )
    (net (code "31") (name "/IO21_R6") (class "Default")
      (node (ref "JP1") (pin "P$30") (pinfunction "R6_P$30") (pintype "bidirectional"))
      (node (ref "U2") (pin "23") (pinfunction "IO21_23") (pintype "bidirectional"))
    )
    (net (code "32") (name "/IO35_I2S_BCLK") (class "Default")
      (node (ref "R19") (pin "2") (pinfunction "2_2") (pintype "passive"))
      (node (ref "U2") (pin "28") (pinfunction "NC1_28") (pintype "bidirectional"))
    )
    (net (code "33") (name "/IO36_TP_IRQ") (class "Default")
      (node (ref "R30") (pin "1") (pinfunction "1_1") (pintype "passive"))
      (node (ref "U2") (pin "29") (pinfunction "NC2_29") (pintype "bidirectional"))
      (node (ref "U41") (pin "11") (pinfunction "PENIRQ_11") (pintype "bidirectional"))
    )
    (net (code "34") (name "/IO37_I2C_SDA") (class "Default")
      (node (ref "J4") (pin "8") (pinfunction "P$8_8") (pintype "bidirectional"))
      (node (ref "J7") (pin "2") (pinfunction "2_2") (pintype "bidirectional"))
      (node (ref "R7") (pin "2") (pinfunction "2_2") (pintype "passive"))
      (node (ref "U2") (pin "30") (pinfunction "NC3_30") (pintype "bidirectional"))
    )
    (net (code "35") (name "/IO38_I2C_SCL") (class "Default")
      (node (ref "J4") (pin "7") (pinfunction "P$7_7") (pintype "bidirectional"))
      (node (ref "J7") (pin "1") (pinfunction "1_1") (pintype "bidirectional"))
      (node (ref "R6") (pin "2") (pinfunction "2_2") (pintype "passive"))
      (node (ref "U2") (pin "31") (pinfunction "IO38_31") (pintype "bidirectional"))
    )
    (net (code "36") (name "/IO39_HSYNC") (class "Default")
      (node (ref "JP1") (pin "P$9") (pinfunction "HSYNC_P$9") (pintype "bidirectional"))
      (node (ref "U2") (pin "32") (pinfunction "IO39_32") (pintype "bidirectional"))
    )
    (net (code "37") (name "/IO40_DE") (class "Default")
      (node (ref "JP1") (pin "P$7") (pinfunction "DE_P$7") (pintype "bidirectional"))
      (node (ref "U2") (pin "33") (pinfunction "IO40_33") (pintype "bidirectional"))
    )
    (net (code "38") (name "/IO41_VSYNC") (class "Default")
      (node (ref "JP1") (pin "P$8") (pinfunction "VSYNC_P$8") (pintype "bidirectional"))
      (node (ref "U2") (pin "34") (pinfunction "IO41_34") (pintype "bidirectional"))
    )
    (net (code "39") (name "/IO42_CLK_DCLK") (class "Default")
      (node (ref "R26") (pin "1") (pinfunction "1_1") (pintype "passive"))
      (node (ref "U2") (pin "35") (pinfunction "IO42_35") (pintype "bidirectional"))
    )
    (net (code "40") (name "/IO45_R3") (class "Default")
      (node (ref "JP1") (pin "P$33") (pinfunction "R3_P$33") (pintype "bidirectional"))
      (node (ref "R31") (pin "2") (pinfunction "2_2") (pintype "passive"))
      (node (ref "U2") (pin "26") (pinfunction "IO45_26") (pintype "bidirectional"))
    )
    (net (code "41") (name "/IO46_B5") (class "Default")
      (node (ref "JP1") (pin "P$15") (pinfunction "B5_P$15") (pintype "bidirectional"))
      (node (ref "U2") (pin "16") (pinfunction "IO46_16") (pintype "bidirectional"))
    )
    (net (code "42") (name "/IO47_R5") (class "Default")
      (node (ref "JP1") (pin "P$31") (pinfunction "R5_P$31") (pintype "bidirectional"))
      (node (ref "U2") (pin "24") (pinfunction "IO47_24") (pintype "bidirectional"))
    )
    (net (code "43") (name "/IO48_R4") (class "Default")
      (node (ref "JP1") (pin "P$32") (pinfunction "R4_P$32") (pintype "bidirectional"))
      (node (ref "U2") (pin "25") (pinfunction "IO48_25") (pintype "bidirectional"))
    )
    (net (code "44") (name "/LCD_LEDA") (class "Default")
      (node (ref "C19") (pin "2") (pinfunction "2_2") (pintype "passive"))
      (node (ref "C21") (pin "2") (pinfunction "2_2") (pintype "passive"))
      (node (ref "D6") (pin "2") (pinfunction "-_2") (pintype "passive"))
      (node (ref "JP1") (pin "P$39") (pinfunction "LEDA_P$39") (pintype "bidirectional"))
      (node (ref "U4") (pin "5") (pinfunction "5-OV_5") (pintype "bidirectional"))
    )
    (net (code "45") (name "/LCD_LEDK") (class "Default")
      (node (ref "JP1") (pin "P$40") (pinfunction "LEDK_P$40") (pintype "bidirectional"))
      (node (ref "R29") (pin "1") (pinfunction "1_1") (pintype "passive"))
      (node (ref "U4") (pin "3") (pinfunction "3-FB_3") (pintype "bidirectional"))
    )
    (net (code "46") (name "/LRCLK") (class "Default")
      (node (ref "R12") (pin "1") (pinfunction "1_1") (pintype "passive"))
      (node (ref "U11") (pin "2") (pinfunction "LRCLK_2") (pintype "bidirectional"))
    )
    (net (code "47") (name "/TP_X+") (class "Default")
      (node (ref "C35") (pin "2") (pinfunction "2_2") (pintype "passive"))
      (node (ref "JP1") (pin "P$4") (pinfunction "XR_P$4") (pintype "bidirectional"))
      (node (ref "U41") (pin "2") (pinfunction "XP_2") (pintype "bidirectional"))
    )
    (net (code "48") (name "/TP_X-") (class "Default")
      (node (ref "C27") (pin "2") (pinfunction "2_2") (pintype "passive"))
      (node (ref "JP1") (pin "P$2") (pinfunction "XL_P$2") (pintype "bidirectional"))
      (node (ref "U41") (pin "4") (pinfunction "XN_4") (pintype "bidirectional"))
    )
    (net (code "49") (name "/TP_Y+") (class "Default")
      (node (ref "C28") (pin "2") (pinfunction "2_2") (pintype "passive"))
      (node (ref "JP1") (pin "P$3") (pinfunction "YD_P$3") (pintype "bidirectional"))
      (node (ref "U41") (pin "3") (pinfunction "YP_3") (pintype "bidirectional"))
    )
    (net (code "50") (name "/TP_Y-") (class "Default")
      (node (ref "C22") (pin "2") (pinfunction "2_2") (pintype "passive"))
      (node (ref "JP1") (pin "P$1") (pinfunction "YU_P$1") (pintype "bidirectional"))
      (node (ref "U41") (pin "5") (pinfunction "YN_5") (pintype "bidirectional"))
    )
    (net (code "51") (name "/UART0_RXD0") (class "Default")
      (node (ref "R72") (pin "1") (pinfunction "1_1") (pintype "passive"))
      (node (ref "U2") (pin "36") (pinfunction "RXD0_36") (pintype "bidirectional"))
    )
    (net (code "52") (name "/UART0_TXD0") (class "Default")
      (node (ref "R71") (pin "1") (pinfunction "1_1") (pintype "passive"))
      (node (ref "U2") (pin "37") (pinfunction "TXD0_37") (pintype "bidirectional"))
    )
    (net (code "53") (name "/USB_D+") (class "Default")
      (node (ref "R9") (pin "2") (pinfunction "2_2") (pintype "passive"))
      (node (ref "U6") (pin "5") (pinfunction "UD+_5") (pintype "bidirectional"))
    )
    (net (code "54") (name "/USB_D-") (class "Default")
      (node (ref "R8") (pin "2") (pinfunction "2_2") (pintype "passive"))
      (node (ref "U6") (pin "6") (pinfunction "UD-_6") (pintype "bidirectional"))
    )
    (net (code "55") (name "/VBUS") (class "Default")
      (node (ref "D3") (pin "1") (pinfunction "+_1") (pintype "passive"))
      (node (ref "J3") (pin "A4") (pinfunction "VBUS_A4") (pintype "bidirectional"))
      (node (ref "J3") (pin "A9") (pinfunction "VBUS_A9") (pintype "bidirectional"))
      (node (ref "J3") (pin "B4") (pinfunction "VBUS_B4") (pintype "bidirectional"))
      (node (ref "J3") (pin "B9") (pinfunction "VBUS_B9") (pintype "bidirectional"))
      (node (ref "R15") (pin "2") (pinfunction "2_2") (pintype "passive"))
      (node (ref "U8") (pin "P$4") (pinfunction "4_G_P$4") (pintype "bidirectional"))
    )
    (net (code "56") (name "/VDD") (class "Default")
      (node (ref "C24") (pin "1") (pinfunction "1_1") (pintype "passive"))
      (node (ref "C25") (pin "1") (pinfunction "1_1") (pintype "passive"))
      (node (ref "R10") (pin "2") (pinfunction "2_2") (pintype "passive"))
      (node (ref "R18/NC") (pin "2") (pinfunction "2_2") (pintype "passive"))
      (node (ref "U11") (pin "6") (pinfunction "VDD_6") (pintype "bidirectional"))
    )
    (net (code "57") (name "/VIN") (class "Default")
      (node (ref "C42") (pin "2") (pinfunction "2_2") (pintype "passive"))
      (node (ref "C6") (pin "2") (pinfunction "2_2") (pintype "passive"))
      (node (ref "D3") (pin "2") (pinfunction "-_2") (pintype "passive"))
      (node (ref "Q30") (pin "2") (pinfunction "S_2") (pintype "bidirectional"))
      (node (ref "R172") (pin "1") (pinfunction "1_1") (pintype "passive"))
      (node (ref "R18/NC") (pin "1") (pinfunction "1_1") (pintype "passive"))
      (node (ref "U1") (pin "1") (pinfunction "EN_1") (pintype "bidirectional"))
      (node (ref "U1") (pin "4") (pinfunction "VIN_4") (pintype "bidirectional"))
      (node (ref "U8") (pin "P$1") (pinfunction "1_S_P$1") (pintype "bidirectional"))
      (node (ref "U8") (pin "P$2") (pinfunction "2_S_P$2") (pintype "bidirectional"))
      (node (ref "U8") (pin "P$3") (pinfunction "3_S_P$3") (pintype "bidirectional"))
    )
    (net (code "58") (name "/VIN2") (class "Default")
      (node (ref "C18") (pin "2") (pinfunction "2_2") (pintype "passive"))
      (node (ref "C43") (pin "2") (pinfunction "2_2") (pintype "passive"))
      (node (ref "L5") (pin "1") (pinfunction "1_1") (pintype "bidirectional"))
      (node (ref "Q30") (pin "3") (pinfunction "D_3") (pintype "bidirectional"))
      (node (ref "U4") (pin "6") (pinfunction "6-VIN_6") (pintype "bidirectional"))
    )
    (net (code "59") (name "GND") (class "Default")
      (node (ref "C10") (pin "1") (pinfunction "1_1") (pintype "passive"))
      (node (ref "C11") (pin "2") (pinfunction "2_2") (pintype "passive"))
      (node (ref "C12") (pin "1") (pinfunction "1_1") (pintype "passive"))
      (node (ref "C13") (pin "2") (pinfunction "2_2") (pintype "passive"))
      (node (ref "C14") (pin "2") (pinfunction "2_2") (pintype "passive"))
      (node (ref "C15") (pin "1") (pinfunction "1_1") (pintype "passive"))
      (node (ref "C16") (pin "2") (pinfunction "2_2") (pintype "passive"))
      (node (ref "C17") (pin "1") (pinfunction "1_1") (pintype "passive"))
      (node (ref "C18") (pin "1") (pinfunction "1_1") (pintype "passive"))
      (node (ref "C19") (pin "1") (pinfunction "1_1") (pintype "passive"))
      (node (ref "C2") (pin "2") (pinfunction "2_2") (pintype "passive"))
      (node (ref "C20") (pin "2") (pinfunction "2_2") (pintype "passive"))
      (node (ref "C21") (pin "1") (pinfunction "1_1") (pintype "passive"))
      (node (ref "C22") (pin "1") (pinfunction "1_1") (pintype "passive"))
      (node (ref "C23") (pin "1") (pinfunction "1_1") (pintype "passive"))
      (node (ref "C24") (pin "2") (pinfunction "2_2") (pintype "passive"))
      (node (ref "C25") (pin "2") (pinfunction "2_2") (pintype "passive"))
      (node (ref "C26") (pin "2") (pinfunction "2_2") (pintype "passive"))
      (node (ref "C27") (pin "1") (pinfunction "1_1") (pintype "passive"))
      (node (ref "C28") (pin "1") (pinfunction "1_1") (pintype "passive"))
      (node (ref "C29") (pin "1") (pinfunction "1_1") (pintype "passive"))
      (node (ref "C3") (pin "2") (pinfunction "2_2") (pintype "passive"))
      (node (ref "C30") (pin "1") (pinfunction "1_1") (pintype "passive"))
      (node (ref "C31") (pin "1") (pinfunction "1_1") (pintype "passive"))
      (node (ref "C32") (pin "1") (pinfunction "1_1") (pintype "passive"))
      (node (ref "C33") (pin "2") (pinfunction "2_2") (pintype "passive"))
      (node (ref "C35") (pin "1") (pinfunction "1_1") (pintype "passive"))
      (node (ref "C36") (pin "1") (pinfunction "1_1") (pintype "passive"))
      (node (ref "C4") (pin "1") (pinfunction "1_1") (pintype "passive"))
      (node (ref "C42") (pin "1") (pinfunction "1_1") (pintype "passive"))
      (node (ref "C43") (pin "1") (pinfunction "1_1") (pintype "passive"))
      (node (ref "C54") (pin "1") (pinfunction "1_1") (pintype "passive"))
      (node (ref "C6") (pin "1") (pinfunction "1_1") (pintype "passive"))
      (node (ref "C7") (pin "1") (pinfunction "1_1") (pintype "passive"))
      (node (ref "C8") (pin "1") (pinfunction "1_1") (pintype "passive"))
      (node (ref "C9") (pin "1") (pinfunction "1_1") (pintype "passive"))
      (node (ref "J1") (pin "P$2") (pinfunction "P$2_P$2") (pintype "bidirectional"))
      (node (ref "J1") (pin "P$3") (pinfunction "P$3_P$3") (pintype "bidirectional"))
      (node (ref "J1") (pin "P$4") (pinfunction "P$4_P$4") (pintype "bidirectional"))
      (node (ref "J10") (pin "4") (pinfunction "4_4") (pintype "bidirectional"))
      (node (ref "J10") (pin "SS1") (pinfunction "SS1_SS1") (pintype "bidirectional"))
      (node (ref "J10") (pin "SS2") (pinfunction "SS2_SS2") (pintype "bidirectional"))
      (node (ref "J3") (pin "A1") (pinfunction "GND_A1") (pintype "bidirectional"))
      (node (ref "J3") (pin "A12") (pinfunction "GND_A12") (pintype "bidirectional"))
      (node (ref "J3") (pin "B1") (pinfunction "GND_B1") (pintype "bidirectional"))
      (node (ref "J3") (pin "B12") (pinfunction "GND_B12") (pintype "bidirectional"))
      (node (ref "J3") (pin "P$6") (pinfunction "P$17_P$6") (pintype "bidirectional"))
      (node (ref "J3") (pin "P$7") (pinfunction "P$18_P$7") (pintype "bidirectional"))
      (node (ref "J3") (pin "P$8") (pinfunction "P$19_P$8") (pintype "bidirectional"))
      (node (ref "J3") (pin "P$9") (pinfunction "P$20_P$9") (pintype "bidirectional"))
      (node (ref "J4") (pin "3") (pinfunction "P$3_3") (pintype "bidirectional"))
      (node (ref "J4") (pin "4") (pinfunction "P$4_4") (pintype "bidirectional"))
      (node (ref "J5") (pin "P$3") (pinfunction "P$3_P$3") (pintype "bidirectional"))
      (node (ref "J5") (pin "P$4") (pinfunction "P$4_P$4") (pintype "bidirectional"))
      (node (ref "J7") (pin "4") (pinfunction "4_4") (pintype "bidirectional"))
      (node (ref "J7") (pin "SS1") (pinfunction "SS1_SS1") (pintype "bidirectional"))
      (node (ref "J7") (pin "SS2") (pinfunction "SS2_SS2") (pintype "bidirectional"))
      (node (ref "JP1") (pin "P$12") (pinfunction "GND4_P$12") (pintype "bidirectional"))
      (node (ref "JP1") (pin "P$18") (pinfunction "B2_P$18") (pintype "bidirectional"))
      (node (ref "JP1") (pin "P$19") (pinfunction "B1_P$19") (pintype "bidirectional"))
      (node (ref "JP1") (pin "P$20") (pinfunction "B0_P$20") (pintype "bidirectional"))
      (node (ref "JP1") (pin "P$27") (pinfunction "G1_P$27") (pintype "bidirectional"))
      (node (ref "JP1") (pin "P$28") (pinfunction "G0_P$28") (pintype "bidirectional"))
      (node (ref "JP1") (pin "P$34") (pinfunction "R2_P$34") (pintype "bidirectional"))
      (node (ref "JP1") (pin "P$35") (pinfunction "R1_P$35") (pintype "bidirectional"))
      (node (ref "JP1") (pin "P$36") (pinfunction "R0_P$36") (pintype "bidirectional"))
      (node (ref "JP1") (pin "P$38") (pinfunction "GND3_P$38") (pintype "bidirectional"))
      (node (ref "JP1") (pin "P$41") (pinfunction "GND5_P$41") (pintype "bidirectional"))
      (node (ref "JP1") (pin "P$42") (pinfunction "GND6_P$42") (pintype "bidirectional"))
      (node (ref "JP1") (pin "P$5") (pinfunction "GND2_P$5") (pintype "bidirectional"))
      (node (ref "K1") (pin "1") (pinfunction "1_1") (pintype "passive"))
      (node (ref "K4") (pin "1") (pinfunction "1_1") (pintype "passive"))
      (node (ref "LED1") (pin "-") (pinfunction "-_-") (pintype "passive"))
      (node (ref "Q5") (pin "2") (pinfunction "E_2") (pintype "passive"))
      (node (ref "R1") (pin "1") (pinfunction "1_1") (pintype "passive"))
      (node (ref "R13") (pin "1") (pinfunction "1_1") (pintype "passive"))
      (node (ref "R14") (pin "2") (pinfunction "2_2") (pintype "passive"))
      (node (ref "R15") (pin "1") (pinfunction "1_1") (pintype "passive"))
      (node (ref "R21") (pin "2") (pinfunction "2_2") (pintype "passive"))
      (node (ref "R29") (pin "2") (pinfunction "2_2") (pintype "passive"))
      (node (ref "R31") (pin "1") (pinfunction "1_1") (pintype "passive"))
      (node (ref "R58") (pin "1") (pinfunction "1_1") (pintype "passive"))
      (node (ref "SD1") (pin "6") (pinfunction "VSS_6") (pintype "bidirectional"))
      (node (ref "SD1") (pin "G1") (pinfunction "G1_G1") (pintype "bidirectional"))
      (node (ref "SD1") (pin "G2") (pinfunction "G2_G2") (pintype "bidirectional"))
      (node (ref "SD1") (pin "G3") (pinfunction "G3_G3") (pintype "bidirectional"))
      (node (ref "SD1") (pin "G4") (pinfunction "G4_G4") (pintype "bidirectional"))
      (node (ref "U1") (pin "2") (pinfunction "GND_2") (pintype "bidirectional"))
      (node (ref "U11") (pin "7") (pinfunction "GND_7") (pintype "bidirectional"))
      (node (ref "U2") (pin "1") (pinfunction "GND1_1") (pintype "bidirectional"))
      (node (ref "U2") (pin "40") (pinfunction "GND2_40") (pintype "bidirectional"))
      (node (ref "U2") (pin "41") (pinfunction "GND3_41") (pintype "bidirectional"))
      (node (ref "U2") (pin "42") (pinfunction "GND4_42") (pintype "bidirectional"))
      (node (ref "U2") (pin "43") (pinfunction "GND5_43") (pintype "bidirectional"))
      (node (ref "U2") (pin "44") (pinfunction "GND6_44") (pintype "bidirectional"))
      (node (ref "U2") (pin "45") (pinfunction "GND7_45") (pintype "bidirectional"))
      (node (ref "U2") (pin "46") (pinfunction "GND8_46") (pintype "bidirectional"))
      (node (ref "U2") (pin "47") (pinfunction "GND9_47") (pintype "bidirectional"))
      (node (ref "U2") (pin "48") (pinfunction "GND10_48") (pintype "bidirectional"))
      (node (ref "U2") (pin "49") (pinfunction "GND11_49") (pintype "bidirectional"))
      (node (ref "U4") (pin "2") (pinfunction "2-GND_2") (pintype "bidirectional"))
      (node (ref "U41") (pin "6") (pinfunction "GND_6") (pintype "bidirectional"))
      (node (ref "U6") (pin "1") (pinfunction "GND_1") (pintype "bidirectional"))
    )
    (net (code "60") (name "Net-(C14-Pad1)") (class "Default")
      (node (ref "C14") (pin "1") (pinfunction "1_1") (pintype "passive"))
      (node (ref "C37") (pin "1") (pinfunction "1_1") (pintype "passive"))
      (node (ref "J5") (pin "P$2") (pinfunction "P$2_P$2") (pintype "bidirectional"))
    )
    (net (code "61") (name "Net-(C16-Pad1)") (class "Default")
      (node (ref "C16") (pin "1") (pinfunction "1_1") (pintype "passive"))
      (node (ref "C38") (pin "1") (pinfunction "1_1") (pintype "passive"))
      (node (ref "J5") (pin "P$1") (pinfunction "P$1_P$1") (pintype "bidirectional"))
    )
    (net (code "62") (name "Net-(D6-+)") (class "Default")
      (node (ref "D6") (pin "1") (pinfunction "+_1") (pintype "passive"))
      (node (ref "L5") (pin "2") (pinfunction "2_2") (pintype "bidirectional"))
      (node (ref "U4") (pin "1") (pinfunction "1-SW_1") (pintype "bidirectional"))
    )
    (net (code "63") (name "Net-(J3-CC1)") (class "Default")
      (node (ref "J3") (pin "A5") (pinfunction "CC1_A5") (pintype "bidirectional"))
      (node (ref "R13") (pin "2") (pinfunction "2_2") (pintype "passive"))
    )
    (net (code "64") (name "Net-(J3-CC2)") (class "Default")
      (node (ref "J3") (pin "B5") (pinfunction "CC2_B5") (pintype "bidirectional"))
      (node (ref "R14") (pin "1") (pinfunction "1_1") (pintype "passive"))
    )
    (net (code "65") (name "Net-(JP1-DISP)") (class "Default")
      (node (ref "JP1") (pin "P$10") (pinfunction "DISP_P$10") (pintype "bidirectional"))
      (node (ref "R25") (pin "2") (pinfunction "2_2") (pintype "passive"))
    )
    (net (code "66") (name "Net-(LED1-Pad+)") (class "Default")
      (node (ref "LED1") (pin "+") (pinfunction "+_+") (pintype "passive"))
      (node (ref "R3") (pin "1") (pinfunction "1_1") (pintype "passive"))
    )
    (net (code "67") (name "Net-(Q5-B)") (class "Default")
      (node (ref "Q5") (pin "1") (pinfunction "B_1") (pintype "passive"))
      (node (ref "R11") (pin "1") (pinfunction "1_1") (pintype "passive"))
      (node (ref "R58") (pin "2") (pinfunction "2_2") (pintype "passive"))
    )
    (net (code "68") (name "Net-(Q30-G)") (class "Default")
      (node (ref "Q30") (pin "1") (pinfunction "G_1") (pintype "bidirectional"))
      (node (ref "Q5") (pin "3") (pinfunction "C_3") (pintype "passive"))
      (node (ref "R172") (pin "2") (pinfunction "2_2") (pintype "passive"))
    )
    (net (code "69") (name "Net-(SD1-DATA1)") (class "Default")
      (node (ref "R17") (pin "2") (pinfunction "2_2") (pintype "passive"))
      (node (ref "SD1") (pin "8") (pinfunction "DATA1_8") (pintype "bidirectional"))
    )
    (net (code "70") (name "Net-(SD1-DATA2)") (class "Default")
      (node (ref "R16") (pin "2") (pinfunction "2_2") (pintype "passive"))
      (node (ref "SD1") (pin "1") (pinfunction "DATA2_1") (pintype "bidirectional"))
    )
    (net (code "71") (name "Net-(U1-FB)") (class "Default")
      (node (ref "R20") (pin "2") (pinfunction "2_2") (pintype "passive"))
      (node (ref "R21") (pin "1") (pinfunction "1_1") (pintype "passive"))
      (node (ref "U1") (pin "5") (pinfunction "FB_5") (pintype "bidirectional"))
    )
    (net (code "72") (name "Net-(U1-SW)") (class "Default")
      (node (ref "L4") (pin "1") (pinfunction "1_1") (pintype "bidirectional"))
      (node (ref "U1") (pin "3") (pinfunction "SW_3") (pintype "bidirectional"))
    )
    (net (code "73") (name "Net-(U6-RXD)") (class "Default")
      (node (ref "R71") (pin "2") (pinfunction "2_2") (pintype "passive"))
      (node (ref "U6") (pin "3") (pinfunction "RXD_3") (pintype "bidirectional"))
    )
    (net (code "74") (name "Net-(U6-TXD)") (class "Default")
      (node (ref "R72") (pin "2") (pinfunction "2_2") (pintype "passive"))
      (node (ref "U6") (pin "2") (pinfunction "TXD_2") (pintype "bidirectional"))
    )
    (net (code "75") (name "Net-(U11-VON)") (class "Default")
      (node (ref "C38") (pin "2") (pinfunction "2_2") (pintype "passive"))
      (node (ref "U11") (pin "5") (pinfunction "VON_5") (pintype "bidirectional"))
    )
    (net (code "76") (name "Net-(U11-VOP)") (class "Default")
      (node (ref "C37") (pin "2") (pinfunction "2_2") (pintype "passive"))
      (node (ref "U11") (pin "8") (pinfunction "VOP_8") (pintype "bidirectional"))
    )
    (net (code "77") (name "Net-(U41-CS)") (class "Default")
      (node (ref "R1") (pin "2") (pinfunction "2_2") (pintype "passive"))
      (node (ref "R2") (pin "2") (pinfunction "2_2") (pintype "passive"))
      (node (ref "U41") (pin "15") (pinfunction "CS_15") (pintype "bidirectional"))
    )
    (net (code "78") (name "Net-(U41-VBAT)") (class "Default")
      (node (ref "R41") (pin "2") (pinfunction "2_2") (pintype "passive"))
      (node (ref "U41") (pin "7") (pinfunction "VBAT_7") (pintype "bidirectional"))
    )
    (net (code "79") (name "unconnected-(J3-SBU1-PadA8)") (class "Default")
      (node (ref "J3") (pin "A8") (pinfunction "SBU1_A8") (pintype "bidirectional"))
    )
    (net (code "80") (name "unconnected-(J3-SBU2-PadB8)") (class "Default")
      (node (ref "J3") (pin "B8") (pinfunction "SBU2_B8") (pintype "bidirectional"))
    )
    (net (code "81") (name "unconnected-(JP1-NC-PadP$6)") (class "Default")
      (node (ref "JP1") (pin "P$6") (pinfunction "NC_P$6") (pintype "bidirectional"))
    )
    (net (code "82") (name "unconnected-(SD1-CDN-Pad9)") (class "Default")
      (node (ref "SD1") (pin "9") (pinfunction "CDN_9") (pintype "bidirectional"))
    )
    (net (code "83") (name "unconnected-(U6-CTS#-Pad9)") (class "Default")
      (node (ref "U6") (pin "9") (pinfunction "CTS#_9") (pintype "bidirectional"))
    )
    (net (code "84") (name "unconnected-(U6-DCD#-Pad12)") (class "Default")
      (node (ref "U6") (pin "12") (pinfunction "DCD#_12") (pintype "bidirectional"))
    )
    (net (code "85") (name "unconnected-(U6-DSR#-Pad10)") (class "Default")
      (node (ref "U6") (pin "10") (pinfunction "DSR#_10") (pintype "bidirectional"))
    )
    (net (code "86") (name "unconnected-(U6-DTR#-Pad13)") (class "Default")
      (node (ref "U6") (pin "13") (pinfunction "DTR#_13") (pintype "bidirectional"))
    )
    (net (code "87") (name "unconnected-(U6-RI#-Pad11)") (class "Default")
      (node (ref "U6") (pin "11") (pinfunction "RI#_11") (pintype "bidirectional"))
    )
    (net (code "88") (name "unconnected-(U6-RS232-Pad15)") (class "Default")
      (node (ref "U6") (pin "15") (pinfunction "RS232_15") (pintype "bidirectional"))
    )
    (net (code "89") (name "unconnected-(U6-RTS#-Pad14)") (class "Default")
      (node (ref "U6") (pin "14") (pinfunction "RTS#_14") (pintype "bidirectional"))
    )
    (net (code "90") (name "unconnected-(U6-XI-Pad7)") (class "Default")
      (node (ref "U6") (pin "7") (pinfunction "XI_7") (pintype "bidirectional"))
    )
    (net (code "91") (name "unconnected-(U6-XO-Pad8)") (class "Default")
      (node (ref "U6") (pin "8") (pinfunction "XO_8") (pintype "bidirectional"))
    )
    (net (code "92") (name "unconnected-(U11-PE-Pad9)") (class "Default")
      (node (ref "U11") (pin "9") (pinfunction "PE_9") (pintype "bidirectional"))
    )
    (net (code "93") (name "unconnected-(U41-BUESY-Pad13)") (class "Default")
      (node (ref "U41") (pin "13") (pinfunction "BUESY_13") (pintype "bidirectional"))
    )
    (net (code "94") (name "unconnected-(U41-IN-Pad8)") (class "Default")
      (node (ref "U41") (pin "8") (pinfunction "IN_8") (pintype "bidirectional"))
    )
  )
)
